# circuit.net
KiCad netlist of a schematic drawn in EAGLE
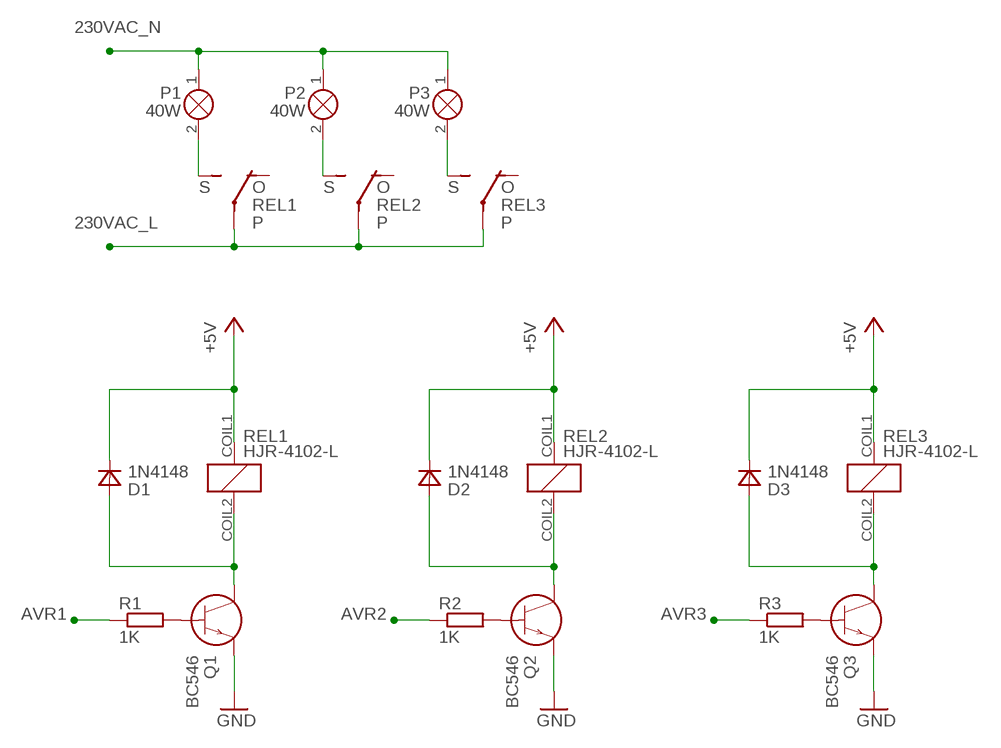
[diagram p0: schematic, sheet 1]

(export (version "E")
  (design (tool "Eeschema 10.0.6"))
  (components
    (comp (ref "D1")
      (value "1N4148")
      (footprint "eagle-import:DIODE")
      (libsource (lib "eagle-import") (part "DIODE"))
    )
    (comp (ref "D2")
      (value "1N4148")
      (footprint "eagle-import:DIODE")
      (libsource (lib "eagle-import") (part "DIODE"))
    )
    (comp (ref "D3")
      (value "1N4148")
      (footprint "eagle-import:DIODE")
      (libsource (lib "eagle-import") (part "DIODE"))
    )
    (comp (ref "P1")
      (value "40W")
      (footprint "eagle-import:LAMPE")
      (libsource (lib "eagle-import") (part "SIGNALLAMPE"))
    )
    (comp (ref "P2")
      (value "40W")
      (footprint "eagle-import:LAMPE")
      (libsource (lib "eagle-import") (part "SIGNALLAMPE"))
    )
    (comp (ref "P3")
      (value "40W")
      (footprint "eagle-import:LAMPE")
      (libsource (lib "eagle-import") (part "SIGNALLAMPE"))
    )
    (comp (ref "Q1")
      (value "BC546")
      (footprint "eagle-import:NPN-TRANSISTOR")
      (libsource (lib "eagle-import") (part "NPN-TRANSISTOR"))
    )
    (comp (ref "Q2")
      (value "BC546")
      (footprint "eagle-import:NPN-TRANSISTOR")
      (libsource (lib "eagle-import") (part "NPN-TRANSISTOR"))
    )
    (comp (ref "Q3")
      (value "BC546")
      (footprint "eagle-import:NPN-TRANSISTOR")
      (libsource (lib "eagle-import") (part "NPN-TRANSISTOR"))
    )
    (comp (ref "R1")
      (value "1K")
      (footprint "eagle-import:0207_15")
      (libsource (lib "eagle-import") (part "R-EU_0207/15"))
    )
    (comp (ref "R2")
      (value "1K")
      (footprint "eagle-import:0207_15")
      (libsource (lib "eagle-import") (part "R-EU_0207/15"))
    )
    (comp (ref "R3")
      (value "1K")
      (footprint "eagle-import:0207_15")
      (libsource (lib "eagle-import") (part "R-EU_0207/15"))
    )
    (comp (ref "REL1")
      (value "HJR-4102-L")
      (footprint "eagle-import:HJR4102")
      (libsource (lib "eagle-import") (part "HJR-4102-L"))
    )
    (comp (ref "REL2")
      (value "HJR-4102-L")
      (footprint "eagle-import:HJR4102")
      (libsource (lib "eagle-import") (part "HJR-4102-L"))
    )
    (comp (ref "REL3")
      (value "HJR-4102-L")
      (footprint "eagle-import:HJR4102")
      (libsource (lib "eagle-import") (part "HJR-4102-L"))
    )
  )
  (nets
    (net (code "1") (name "+5V") (class "Default")
      (node (ref "D1") (pin "A") (pinfunction "A_A") (pintype "input"))
      (node (ref "D2") (pin "A") (pinfunction "A_A") (pintype "input"))
      (node (ref "D3") (pin "A") (pinfunction "A_A") (pintype "input"))
      (node (ref "REL1") (pin "COIL1") (pinfunction "1_COIL1") (pintype "passive"))
      (node (ref "REL2") (pin "COIL1") (pinfunction "1_COIL1") (pintype "passive"))
      (node (ref "REL3") (pin "COIL1") (pinfunction "1_COIL1") (pintype "passive"))
    )
    (net (code "2") (name "/230VAC_L") (class "Default")
      (node (ref "REL1") (pin "CENTER1") (pinfunction "P_CENTER1") (pintype "passive"))
      (node (ref "REL1") (pin "CENTER2") (pinfunction "P2_CENTER2") (pintype "bidirectional"))
      (node (ref "REL2") (pin "CENTER1") (pinfunction "P_CENTER1") (pintype "passive"))
      (node (ref "REL2") (pin "CENTER2") (pinfunction "P2_CENTER2") (pintype "bidirectional"))
      (node (ref "REL3") (pin "CENTER1") (pinfunction "P_CENTER1") (pintype "passive"))
      (node (ref "REL3") (pin "CENTER2") (pinfunction "P2_CENTER2") (pintype "bidirectional"))
    )
    (net (code "3") (name "/230VAC_N") (class "Default")
      (node (ref "P1") (pin "1") (pinfunction "X1_1") (pintype "passive"))
      (node (ref "P2") (pin "1") (pinfunction "X1_1") (pintype "passive"))
      (node (ref "P3") (pin "1") (pinfunction "X1_1") (pintype "passive"))
    )
    (net (code "4") (name "/AVR1") (class "Default")
      (node (ref "R1") (pin "1") (pinfunction "1_1") (pintype "passive"))
    )
    (net (code "5") (name "/AVR2") (class "Default")
      (node (ref "R2") (pin "1") (pinfunction "1_1") (pintype "passive"))
    )
    (net (code "6") (name "/AVR3") (class "Default")
      (node (ref "R3") (pin "1") (pinfunction "1_1") (pintype "passive"))
    )
    (net (code "7") (name "GND") (class "Default")
      (node (ref "Q1") (pin "E") (pinfunction "E_E") (pintype "input"))
      (node (ref "Q2") (pin "E") (pinfunction "E_E") (pintype "input"))
      (node (ref "Q3") (pin "E") (pinfunction "E_E") (pintype "input"))
    )
    (net (code "8") (name "Net-(P1-X2)") (class "Default")
      (node (ref "P1") (pin "2") (pinfunction "X2_2") (pintype "passive"))
      (node (ref "REL1") (pin "CON1DEFAULT") (pinfunction "S_CON1DEFAULT") (pintype "passive"))
    )
    (net (code "9") (name "Net-(P2-X2)") (class "Default")
      (node (ref "P2") (pin "2") (pinfunction "X2_2") (pintype "passive"))
      (node (ref "REL2") (pin "CON1DEFAULT") (pinfunction "S_CON1DEFAULT") (pintype "passive"))
    )
    (net (code "10") (name "Net-(P3-X2)") (class "Default")
      (node (ref "P3") (pin "2") (pinfunction "X2_2") (pintype "passive"))
      (node (ref "REL3") (pin "CON1DEFAULT") (pinfunction "S_CON1DEFAULT") (pintype "passive"))
    )
    (net (code "11") (name "Net-(Q1-PadB)") (class "Default")
      (node (ref "Q1") (pin "B") (pinfunction "B_B") (pintype "input"))
      (node (ref "R1") (pin "2") (pinfunction "2_2") (pintype "passive"))
    )
    (net (code "12") (name "Net-(Q2-PadB)") (class "Default")
      (node (ref "Q2") (pin "B") (pinfunction "B_B") (pintype "input"))
      (node (ref "R2") (pin "2") (pinfunction "2_2") (pintype "passive"))
    )
    (net (code "13") (name "Net-(Q3-PadB)") (class "Default")
      (node (ref "Q3") (pin "B") (pinfunction "B_B") (pintype "input"))
      (node (ref "R3") (pin "2") (pinfunction "2_2") (pintype "passive"))
    )
    (net (code "14") (name "Net-(REL1A-2)") (class "Default")
      (node (ref "D1") (pin "C") (pinfunction "C_C") (pintype "input"))
      (node (ref "Q1") (pin "C") (pinfunction "C_C") (pintype "input"))
      (node (ref "REL1") (pin "COIL2") (pinfunction "2_COIL2") (pintype "passive"))
    )
    (net (code "15") (name "Net-(REL2A-2)") (class "Default")
      (node (ref "D2") (pin "C") (pinfunction "C_C") (pintype "input"))
      (node (ref "Q2") (pin "C") (pinfunction "C_C") (pintype "input"))
      (node (ref "REL2") (pin "COIL2") (pinfunction "2_COIL2") (pintype "passive"))
    )
    (net (code "16") (name "Net-(REL3A-2)") (class "Default")
      (node (ref "D3") (pin "C") (pinfunction "C_C") (pintype "input"))
      (node (ref "Q3") (pin "C") (pinfunction "C_C") (pintype "input"))
      (node (ref "REL3") (pin "COIL2") (pinfunction "2_COIL2") (pintype "passive"))
    )
    (net (code "17") (name "unconnected-(REL1B-O-PadCON2OPTION)") (class "Default")
      (node (ref "REL1") (pin "CON2OPTION") (pinfunction "O_CON2OPTION") (pintype "passive"))
    )
    (net (code "18") (name "unconnected-(REL2B-O-PadCON2OPTION)") (class "Default")
      (node (ref "REL2") (pin "CON2OPTION") (pinfunction "O_CON2OPTION") (pintype "passive"))
    )
    (net (code "19") (name "unconnected-(REL3B-O-PadCON2OPTION)") (class "Default")
      (node (ref "REL3") (pin "CON2OPTION") (pinfunction "O_CON2OPTION") (pintype "passive"))
    )
  )
)
